# POWER.net
KiCad netlist of a schematic drawn in Altium Designer
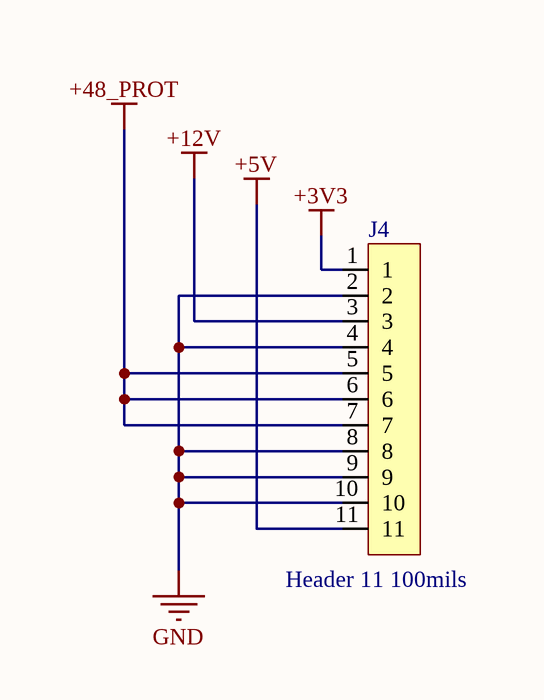
[diagram p0: POWER.SchDoc]

(export (version "E")
  (design (tool "Eeschema 10.0.6"))
  (components
    (comp (ref "J4")
      (value "Header 11 100mils")
      (footprint "Header 11 pos Male 2.54")
      (description "HEADER 11 pins Male 2.54MM")
      (fields
        (field (name "MANUFACTURER") "Sullins")
        (field (name "MANUFACTURER PART NUMBER") "PREC011SAAN-RC")
      )
      (libsource (lib "FedericosLIBSCH") (part "PREC011SAAN-RC"))
    )
  )
  (nets
    (net (code "1") (name "+3V3") (class "Default")
      (node (ref "J4") (pin "1") (pinfunction "1_1") (pintype "passive"))
    )
    (net (code "2") (name "+5V") (class "Default")
      (node (ref "J4") (pin "11") (pinfunction "11_11") (pintype "passive"))
    )
    (net (code "3") (name "+12V") (class "Default")
      (node (ref "J4") (pin "3") (pinfunction "3_3") (pintype "passive"))
    )
    (net (code "4") (name "+48_PROT") (class "Default")
      (node (ref "J4") (pin "5") (pinfunction "5_5") (pintype "passive"))
      (node (ref "J4") (pin "6") (pinfunction "6_6") (pintype "passive"))
      (node (ref "J4") (pin "7") (pinfunction "7_7") (pintype "passive"))
    )
    (net (code "5") (name "GND") (class "Default")
      (node (ref "J4") (pin "10") (pinfunction "10_10") (pintype "passive"))
      (node (ref "J4") (pin "2") (pinfunction "2_2") (pintype "passive"))
      (node (ref "J4") (pin "4") (pinfunction "4_4") (pintype "passive"))
      (node (ref "J4") (pin "8") (pinfunction "8_8") (pintype "passive"))
      (node (ref "J4") (pin "9") (pinfunction "9_9") (pintype "passive"))
    )
  )
)
